# FET_M1.net
KiCad netlist of a schematic drawn in Altium Designer
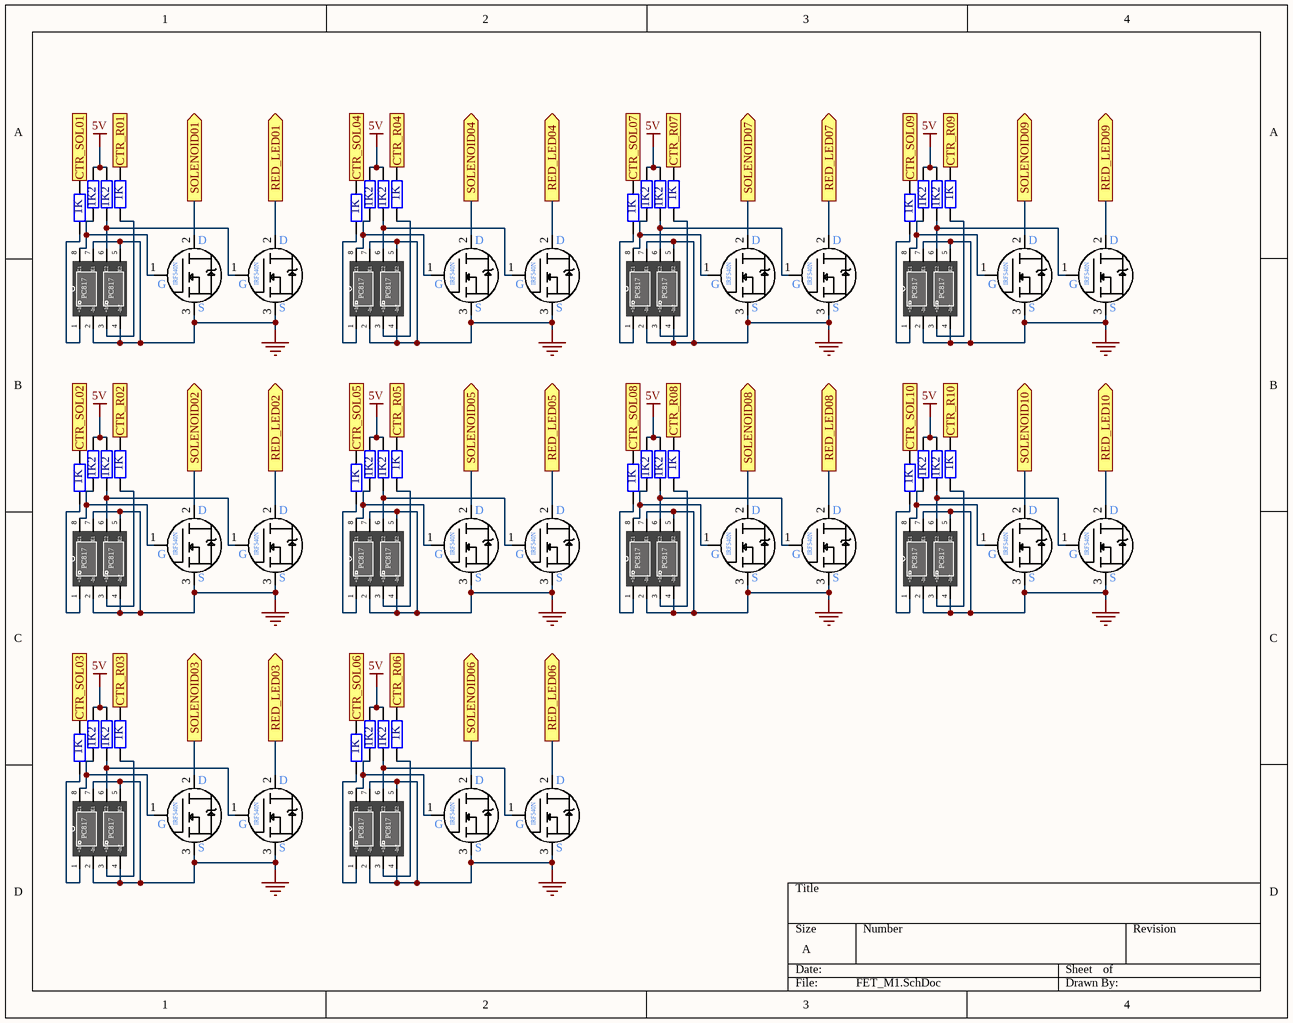
[diagram p0: FET_M1.SchDoc]

(export (version "E")
  (design (tool "Eeschema 10.0.6"))
  (components
    (comp (ref "FET1") (value "5#IRF540N") (footprint "5#IRF540N") (libsource (lib "Sch") (part "5#IRF540N")))
    (comp (ref "FET2") (value "5#IRF540N") (footprint "5#IRF540N") (libsource (lib "Sch") (part "5#IRF540N")))
    (comp (ref "FET3") (value "5#IRF540N") (footprint "5#IRF540N") (libsource (lib "Sch") (part "5#IRF540N")))
    (comp (ref "FET4") (value "5#IRF540N") (footprint "5#IRF540N") (libsource (lib "Sch") (part "5#IRF540N")))
    (comp (ref "FET5") (value "5#IRF540N") (footprint "5#IRF540N") (libsource (lib "Sch") (part "5#IRF540N")))
    (comp (ref "FET6") (value "5#IRF540N") (footprint "5#IRF540N") (libsource (lib "Sch") (part "5#IRF540N")))
    (comp (ref "FET7") (value "5#IRF540N") (footprint "5#IRF540N") (libsource (lib "Sch") (part "5#IRF540N")))
    (comp (ref "FET8") (value "5#IRF540N") (footprint "5#IRF540N") (libsource (lib "Sch") (part "5#IRF540N")))
    (comp (ref "FET9") (value "5#IRF540N") (footprint "5#IRF540N") (libsource (lib "Sch") (part "5#IRF540N")))
    (comp (ref "FET10")
      (value "5#IRF540N")
      (footprint "5#IRF540N")
      (libsource (lib "Sch") (part "5#IRF540N"))
    )
    (comp (ref "FET11")
      (value "5#IRF540N")
      (footprint "5#IRF540N")
      (libsource (lib "Sch") (part "5#IRF540N"))
    )
    (comp (ref "FET12")
      (value "5#IRF540N")
      (footprint "5#IRF540N")
      (libsource (lib "Sch") (part "5#IRF540N"))
    )
    (comp (ref "FET13")
      (value "5#IRF540N")
      (footprint "5#IRF540N")
      (libsource (lib "Sch") (part "5#IRF540N"))
    )
    (comp (ref "FET14")
      (value "5#IRF540N")
      (footprint "5#IRF540N")
      (libsource (lib "Sch") (part "5#IRF540N"))
    )
    (comp (ref "FET15")
      (value "5#IRF540N")
      (footprint "5#IRF540N")
      (libsource (lib "Sch") (part "5#IRF540N"))
    )
    (comp (ref "FET16")
      (value "5#IRF540N")
      (footprint "5#IRF540N")
      (libsource (lib "Sch") (part "5#IRF540N"))
    )
    (comp (ref "FET17")
      (value "5#IRF540N")
      (footprint "5#IRF540N")
      (libsource (lib "Sch") (part "5#IRF540N"))
    )
    (comp (ref "FET18")
      (value "5#IRF540N")
      (footprint "5#IRF540N")
      (libsource (lib "Sch") (part "5#IRF540N"))
    )
    (comp (ref "FET19")
      (value "5#IRF540N")
      (footprint "5#IRF540N")
      (libsource (lib "Sch") (part "5#IRF540N"))
    )
    (comp (ref "FET20")
      (value "5#IRF540N")
      (footprint "5#IRF540N")
      (libsource (lib "Sch") (part "5#IRF540N"))
    )
    (comp (ref "PC1")
      (value "5#Dip8_PC817x2")
      (footprint "5#Dip8_PC817x2")
      (libsource (lib "Sch") (part "5#Dip8_PC817x2"))
    )
    (comp (ref "PC2")
      (value "5#Dip8_PC817x2")
      (footprint "5#Dip8_PC817x2")
      (libsource (lib "Sch") (part "5#Dip8_PC817x2"))
    )
    (comp (ref "PC3")
      (value "5#Dip8_PC817x2")
      (footprint "5#Dip8_PC817x2")
      (libsource (lib "Sch") (part "5#Dip8_PC817x2"))
    )
    (comp (ref "PC4")
      (value "5#Dip8_PC817x2")
      (footprint "5#Dip8_PC817x2")
      (libsource (lib "Sch") (part "5#Dip8_PC817x2"))
    )
    (comp (ref "PC5")
      (value "5#Dip8_PC817x2")
      (footprint "5#Dip8_PC817x2")
      (libsource (lib "Sch") (part "5#Dip8_PC817x2"))
    )
    (comp (ref "PC6")
      (value "5#Dip8_PC817x2")
      (footprint "5#Dip8_PC817x2")
      (libsource (lib "Sch") (part "5#Dip8_PC817x2"))
    )
    (comp (ref "PC7")
      (value "5#Dip8_PC817x2")
      (footprint "5#Dip8_PC817x2")
      (libsource (lib "Sch") (part "5#Dip8_PC817x2"))
    )
    (comp (ref "PC8")
      (value "5#Dip8_PC817x2")
      (footprint "5#Dip8_PC817x2")
      (libsource (lib "Sch") (part "5#Dip8_PC817x2"))
    )
    (comp (ref "PC9")
      (value "5#Dip8_PC817x2")
      (footprint "5#Dip8_PC817x2")
      (libsource (lib "Sch") (part "5#Dip8_PC817x2"))
    )
    (comp (ref "PC10")
      (value "5#Dip8_PC817x2")
      (footprint "5#Dip8_PC817x2")
      (libsource (lib "Sch") (part "5#Dip8_PC817x2"))
    )
    (comp (ref "R18")
      (value "1K")
      (footprint "AXIAL-0.4")
      (description "Resistor")
      (fields (field (name "PUBLISHER") "Altium Limited"))
      (libsource (lib "Miscellaneous Devices") (part "Res2"))
    )
    (comp (ref "R19")
      (value "1K2")
      (footprint "AXIAL-0.4")
      (description "Resistor")
      (fields (field (name "PUBLISHER") "Altium Limited"))
      (libsource (lib "") (part "Res2_1"))
    )
    (comp (ref "R20")
      (value "1K")
      (footprint "AXIAL-0.4")
      (description "Resistor")
      (fields (field (name "PUBLISHER") "Altium Limited"))
      (libsource (lib "Miscellaneous Devices") (part "Res2"))
    )
    (comp (ref "R21")
      (value "1K2")
      (footprint "AXIAL-0.4")
      (description "Resistor")
      (fields (field (name "PUBLISHER") "Altium Limited"))
      (libsource (lib "") (part "Res2_1"))
    )
    (comp (ref "R22")
      (value "1K")
      (footprint "AXIAL-0.4")
      (description "Resistor")
      (fields (field (name "PUBLISHER") "Altium Limited"))
      (libsource (lib "Miscellaneous Devices") (part "Res2"))
    )
    (comp (ref "R23")
      (value "1K2")
      (footprint "AXIAL-0.4")
      (description "Resistor")
      (fields (field (name "PUBLISHER") "Altium Limited"))
      (libsource (lib "") (part "Res2_1"))
    )
    (comp (ref "R24")
      (value "1K")
      (footprint "AXIAL-0.4")
      (description "Resistor")
      (fields (field (name "PUBLISHER") "Altium Limited"))
      (libsource (lib "Miscellaneous Devices") (part "Res2"))
    )
    (comp (ref "R25")
      (value "1K2")
      (footprint "AXIAL-0.4")
      (description "Resistor")
      (fields (field (name "PUBLISHER") "Altium Limited"))
      (libsource (lib "") (part "Res2_1"))
    )
    (comp (ref "R26")
      (value "1K")
      (footprint "AXIAL-0.4")
      (description "Resistor")
      (fields (field (name "PUBLISHER") "Altium Limited"))
      (libsource (lib "Miscellaneous Devices") (part "Res2"))
    )
    (comp (ref "R27")
      (value "1K2")
      (footprint "AXIAL-0.4")
      (description "Resistor")
      (fields (field (name "PUBLISHER") "Altium Limited"))
      (libsource (lib "") (part "Res2_1"))
    )
    (comp (ref "R28")
      (value "1K")
      (footprint "AXIAL-0.4")
      (description "Resistor")
      (fields (field (name "PUBLISHER") "Altium Limited"))
      (libsource (lib "Miscellaneous Devices") (part "Res2"))
    )
    (comp (ref "R29")
      (value "1K2")
      (footprint "AXIAL-0.4")
      (description "Resistor")
      (fields (field (name "PUBLISHER") "Altium Limited"))
      (libsource (lib "") (part "Res2_1"))
    )
    (comp (ref "R30")
      (value "1K")
      (footprint "AXIAL-0.4")
      (description "Resistor")
      (fields (field (name "PUBLISHER") "Altium Limited"))
      (libsource (lib "Miscellaneous Devices") (part "Res2"))
    )
    (comp (ref "R31")
      (value "1K2")
      (footprint "AXIAL-0.4")
      (description "Resistor")
      (fields (field (name "PUBLISHER") "Altium Limited"))
      (libsource (lib "") (part "Res2_1"))
    )
    (comp (ref "R32")
      (value "1K")
      (footprint "AXIAL-0.4")
      (description "Resistor")
      (fields (field (name "PUBLISHER") "Altium Limited"))
      (libsource (lib "Miscellaneous Devices") (part "Res2"))
    )
    (comp (ref "R33")
      (value "1K2")
      (footprint "AXIAL-0.4")
      (description "Resistor")
      (fields (field (name "PUBLISHER") "Altium Limited"))
      (libsource (lib "") (part "Res2_1"))
    )
    (comp (ref "R34")
      (value "1K")
      (footprint "AXIAL-0.4")
      (description "Resistor")
      (fields (field (name "PUBLISHER") "Altium Limited"))
      (libsource (lib "Miscellaneous Devices") (part "Res2"))
    )
    (comp (ref "R35")
      (value "1K2")
      (footprint "AXIAL-0.4")
      (description "Resistor")
      (fields (field (name "PUBLISHER") "Altium Limited"))
      (libsource (lib "") (part "Res2_1"))
    )
    (comp (ref "R36")
      (value "1K")
      (footprint "AXIAL-0.4")
      (description "Resistor")
      (fields (field (name "PUBLISHER") "Altium Limited"))
      (libsource (lib "Miscellaneous Devices") (part "Res2"))
    )
    (comp (ref "R37")
      (value "1K2")
      (footprint "AXIAL-0.4")
      (description "Resistor")
      (fields (field (name "PUBLISHER") "Altium Limited"))
      (libsource (lib "") (part "Res2_1"))
    )
    (comp (ref "R38")
      (value "1K")
      (footprint "AXIAL-0.4")
      (description "Resistor")
      (fields (field (name "PUBLISHER") "Altium Limited"))
      (libsource (lib "Miscellaneous Devices") (part "Res2"))
    )
    (comp (ref "R39")
      (value "1K2")
      (footprint "AXIAL-0.4")
      (description "Resistor")
      (fields (field (name "PUBLISHER") "Altium Limited"))
      (libsource (lib "") (part "Res2_1"))
    )
    (comp (ref "R40")
      (value "1K")
      (footprint "AXIAL-0.4")
      (description "Resistor")
      (fields (field (name "PUBLISHER") "Altium Limited"))
      (libsource (lib "Miscellaneous Devices") (part "Res2"))
    )
    (comp (ref "R41")
      (value "1K2")
      (footprint "AXIAL-0.4")
      (description "Resistor")
      (fields (field (name "PUBLISHER") "Altium Limited"))
      (libsource (lib "") (part "Res2_1"))
    )
    (comp (ref "R42")
      (value "1K")
      (footprint "AXIAL-0.4")
      (description "Resistor")
      (fields (field (name "PUBLISHER") "Altium Limited"))
      (libsource (lib "Miscellaneous Devices") (part "Res2"))
    )
    (comp (ref "R43")
      (value "1K2")
      (footprint "AXIAL-0.4")
      (description "Resistor")
      (fields (field (name "PUBLISHER") "Altium Limited"))
      (libsource (lib "") (part "Res2_1"))
    )
    (comp (ref "R44")
      (value "1K")
      (footprint "AXIAL-0.4")
      (description "Resistor")
      (fields (field (name "PUBLISHER") "Altium Limited"))
      (libsource (lib "Miscellaneous Devices") (part "Res2"))
    )
    (comp (ref "R45")
      (value "1K2")
      (footprint "AXIAL-0.4")
      (description "Resistor")
      (fields (field (name "PUBLISHER") "Altium Limited"))
      (libsource (lib "") (part "Res2_1"))
    )
    (comp (ref "R46")
      (value "1K")
      (footprint "AXIAL-0.4")
      (description "Resistor")
      (fields (field (name "PUBLISHER") "Altium Limited"))
      (libsource (lib "Miscellaneous Devices") (part "Res2"))
    )
    (comp (ref "R47")
      (value "1K2")
      (footprint "AXIAL-0.4")
      (description "Resistor")
      (fields (field (name "PUBLISHER") "Altium Limited"))
      (libsource (lib "") (part "Res2_1"))
    )
    (comp (ref "R48")
      (value "1K")
      (footprint "AXIAL-0.4")
      (description "Resistor")
      (fields (field (name "PUBLISHER") "Altium Limited"))
      (libsource (lib "Miscellaneous Devices") (part "Res2"))
    )
    (comp (ref "R49")
      (value "1K2")
      (footprint "AXIAL-0.4")
      (description "Resistor")
      (fields (field (name "PUBLISHER") "Altium Limited"))
      (libsource (lib "") (part "Res2_1"))
    )
    (comp (ref "R50")
      (value "1K")
      (footprint "AXIAL-0.4")
      (description "Resistor")
      (fields (field (name "PUBLISHER") "Altium Limited"))
      (libsource (lib "Miscellaneous Devices") (part "Res2"))
    )
    (comp (ref "R51")
      (value "1K2")
      (footprint "AXIAL-0.4")
      (description "Resistor")
      (fields (field (name "PUBLISHER") "Altium Limited"))
      (libsource (lib "") (part "Res2_1"))
    )
    (comp (ref "R52")
      (value "1K")
      (footprint "AXIAL-0.4")
      (description "Resistor")
      (fields (field (name "PUBLISHER") "Altium Limited"))
      (libsource (lib "Miscellaneous Devices") (part "Res2"))
    )
    (comp (ref "R53")
      (value "1K2")
      (footprint "AXIAL-0.4")
      (description "Resistor")
      (fields (field (name "PUBLISHER") "Altium Limited"))
      (libsource (lib "") (part "Res2_1"))
    )
    (comp (ref "R54")
      (value "1K")
      (footprint "AXIAL-0.4")
      (description "Resistor")
      (fields (field (name "PUBLISHER") "Altium Limited"))
      (libsource (lib "Miscellaneous Devices") (part "Res2"))
    )
    (comp (ref "R55")
      (value "1K2")
      (footprint "AXIAL-0.4")
      (description "Resistor")
      (fields (field (name "PUBLISHER") "Altium Limited"))
      (libsource (lib "") (part "Res2_1"))
    )
    (comp (ref "R56")
      (value "1K")
      (footprint "AXIAL-0.4")
      (description "Resistor")
      (fields (field (name "PUBLISHER") "Altium Limited"))
      (libsource (lib "Miscellaneous Devices") (part "Res2"))
    )
    (comp (ref "R57")
      (value "1K2")
      (footprint "AXIAL-0.4")
      (description "Resistor")
      (fields (field (name "PUBLISHER") "Altium Limited"))
      (libsource (lib "") (part "Res2_1"))
    )
  )
  (nets
    (net (code "1") (name "/CTR_R01") (class "Default")
      (node (ref "R26") (pin "1") (pinfunction "1_1") (pintype "passive"))
    )
    (net (code "2") (name "/CTR_R02") (class "Default")
      (node (ref "R28") (pin "1") (pinfunction "1_1") (pintype "passive"))
    )
    (net (code "3") (name "/CTR_R03") (class "Default")
      (node (ref "R30") (pin "1") (pinfunction "1_1") (pintype "passive"))
    )
    (net (code "4") (name "/CTR_R04") (class "Default")
      (node (ref "R32") (pin "1") (pinfunction "1_1") (pintype "passive"))
    )
    (net (code "5") (name "/CTR_R05") (class "Default")
      (node (ref "R42") (pin "1") (pinfunction "1_1") (pintype "passive"))
    )
    (net (code "6") (name "/CTR_R06") (class "Default")
      (node (ref "R44") (pin "1") (pinfunction "1_1") (pintype "passive"))
    )
    (net (code "7") (name "/CTR_R07") (class "Default")
      (node (ref "R46") (pin "1") (pinfunction "1_1") (pintype "passive"))
    )
    (net (code "8") (name "/CTR_R08") (class "Default")
      (node (ref "R48") (pin "1") (pinfunction "1_1") (pintype "passive"))
    )
    (net (code "9") (name "/CTR_R09") (class "Default")
      (node (ref "R54") (pin "1") (pinfunction "1_1") (pintype "passive"))
    )
    (net (code "10") (name "/CTR_R10") (class "Default")
      (node (ref "R56") (pin "1") (pinfunction "1_1") (pintype "passive"))
    )
    (net (code "11") (name "/CTR_SOL01") (class "Default")
      (node (ref "R18") (pin "1") (pinfunction "1_1") (pintype "passive"))
    )
    (net (code "12") (name "/CTR_SOL02") (class "Default")
      (node (ref "R20") (pin "1") (pinfunction "1_1") (pintype "passive"))
    )
    (net (code "13") (name "/CTR_SOL03") (class "Default")
      (node (ref "R22") (pin "1") (pinfunction "1_1") (pintype "passive"))
    )
    (net (code "14") (name "/CTR_SOL04") (class "Default")
      (node (ref "R24") (pin "1") (pinfunction "1_1") (pintype "passive"))
    )
    (net (code "15") (name "/CTR_SOL05") (class "Default")
      (node (ref "R34") (pin "1") (pinfunction "1_1") (pintype "passive"))
    )
    (net (code "16") (name "/CTR_SOL06") (class "Default")
      (node (ref "R36") (pin "1") (pinfunction "1_1") (pintype "passive"))
    )
    (net (code "17") (name "/CTR_SOL07") (class "Default")
      (node (ref "R38") (pin "1") (pinfunction "1_1") (pintype "passive"))
    )
    (net (code "18") (name "/CTR_SOL08") (class "Default")
      (node (ref "R40") (pin "1") (pinfunction "1_1") (pintype "passive"))
    )
    (net (code "19") (name "/CTR_SOL09") (class "Default")
      (node (ref "R50") (pin "1") (pinfunction "1_1") (pintype "passive"))
    )
    (net (code "20") (name "/CTR_SOL10") (class "Default")
      (node (ref "R52") (pin "1") (pinfunction "1_1") (pintype "passive"))
    )
    (net (code "21") (name "/RED_LED01") (class "Default")
      (node (ref "FET2") (pin "2") (pinfunction "D_2") (pintype "passive"))
    )
    (net (code "22") (name "/RED_LED02") (class "Default")
      (node (ref "FET4") (pin "2") (pinfunction "D_2") (pintype "passive"))
    )
    (net (code "23") (name "/RED_LED03") (class "Default")
      (node (ref "FET6") (pin "2") (pinfunction "D_2") (pintype "passive"))
    )
    (net (code "24") (name "/RED_LED04") (class "Default")
      (node (ref "FET8") (pin "2") (pinfunction "D_2") (pintype "passive"))
    )
    (net (code "25") (name "/RED_LED05") (class "Default")
      (node (ref "FET10") (pin "2") (pinfunction "D_2") (pintype "passive"))
    )
    (net (code "26") (name "/RED_LED06") (class "Default")
      (node (ref "FET12") (pin "2") (pinfunction "D_2") (pintype "passive"))
    )
    (net (code "27") (name "/RED_LED07") (class "Default")
      (node (ref "FET14") (pin "2") (pinfunction "D_2") (pintype "passive"))
    )
    (net (code "28") (name "/RED_LED08") (class "Default")
      (node (ref "FET16") (pin "2") (pinfunction "D_2") (pintype "passive"))
    )
    (net (code "29") (name "/RED_LED09") (class "Default")
      (node (ref "FET18") (pin "2") (pinfunction "D_2") (pintype "passive"))
    )
    (net (code "30") (name "/RED_LED10") (class "Default")
      (node (ref "FET20") (pin "2") (pinfunction "D_2") (pintype "passive"))
    )
    (net (code "31") (name "/SOLENOID01") (class "Default")
      (node (ref "FET1") (pin "2") (pinfunction "D_2") (pintype "passive"))
    )
    (net (code "32") (name "/SOLENOID02") (class "Default")
      (node (ref "FET3") (pin "2") (pinfunction "D_2") (pintype "passive"))
    )
    (net (code "33") (name "/SOLENOID03") (class "Default")
      (node (ref "FET5") (pin "2") (pinfunction "D_2") (pintype "passive"))
    )
    (net (code "34") (name "/SOLENOID04") (class "Default")
      (node (ref "FET7") (pin "2") (pinfunction "D_2") (pintype "passive"))
    )
    (net (code "35") (name "/SOLENOID05") (class "Default")
      (node (ref "FET9") (pin "2") (pinfunction "D_2") (pintype "passive"))
    )
    (net (code "36") (name "/SOLENOID06") (class "Default")
      (node (ref "FET11") (pin "2") (pinfunction "D_2") (pintype "passive"))
    )
    (net (code "37") (name "/SOLENOID07") (class "Default")
      (node (ref "FET13") (pin "2") (pinfunction "D_2") (pintype "passive"))
    )
    (net (code "38") (name "/SOLENOID08") (class "Default")
      (node (ref "FET15") (pin "2") (pinfunction "D_2") (pintype "passive"))
    )
    (net (code "39") (name "/SOLENOID09") (class "Default")
      (node (ref "FET17") (pin "2") (pinfunction "D_2") (pintype "passive"))
    )
    (net (code "40") (name "/SOLENOID10") (class "Default")
      (node (ref "FET19") (pin "2") (pinfunction "D_2") (pintype "passive"))
    )
    (net (code "41") (name "5V") (class "Default")
      (node (ref "R19") (pin "2") (pinfunction "2_2") (pintype "passive"))
      (node (ref "R21") (pin "2") (pinfunction "2_2") (pintype "passive"))
      (node (ref "R23") (pin "2") (pinfunction "2_2") (pintype "passive"))
      (node (ref "R25") (pin "2") (pinfunction "2_2") (pintype "passive"))
      (node (ref "R27") (pin "2") (pinfunction "2_2") (pintype "passive"))
      (node (ref "R29") (pin "2") (pinfunction "2_2") (pintype "passive"))
      (node (ref "R31") (pin "2") (pinfunction "2_2") (pintype "passive"))
      (node (ref "R33") (pin "2") (pinfunction "2_2") (pintype "passive"))
      (node (ref "R35") (pin "2") (pinfunction "2_2") (pintype "passive"))
      (node (ref "R37") (pin "2") (pinfunction "2_2") (pintype "passive"))
      (node (ref "R39") (pin "2") (pinfunction "2_2") (pintype "passive"))
      (node (ref "R41") (pin "2") (pinfunction "2_2") (pintype "passive"))
      (node (ref "R43") (pin "2") (pinfunction "2_2") (pintype "passive"))
      (node (ref "R45") (pin "2") (pinfunction "2_2") (pintype "passive"))
      (node (ref "R47") (pin "2") (pinfunction "2_2") (pintype "passive"))
      (node (ref "R49") (pin "2") (pinfunction "2_2") (pintype "passive"))
      (node (ref "R51") (pin "2") (pinfunction "2_2") (pintype "passive"))
      (node (ref "R53") (pin "2") (pinfunction "2_2") (pintype "passive"))
      (node (ref "R55") (pin "2") (pinfunction "2_2") (pintype "passive"))
      (node (ref "R57") (pin "2") (pinfunction "2_2") (pintype "passive"))
    )
    (net (code "42") (name "GND") (class "Default")
      (node (ref "FET1") (pin "3") (pinfunction "S_3") (pintype "passive"))
      (node (ref "FET10") (pin "3") (pinfunction "S_3") (pintype "passive"))
      (node (ref "FET11") (pin "3") (pinfunction "S_3") (pintype "passive"))
      (node (ref "FET12") (pin "3") (pinfunction "S_3") (pintype "passive"))
      (node (ref "FET13") (pin "3") (pinfunction "S_3") (pintype "passive"))
      (node (ref "FET14") (pin "3") (pinfunction "S_3") (pintype "passive"))
      (node (ref "FET15") (pin "3") (pinfunction "S_3") (pintype "passive"))
      (node (ref "FET16") (pin "3") (pinfunction "S_3") (pintype "passive"))
      (node (ref "FET17") (pin "3") (pinfunction "S_3") (pintype "passive"))
      (node (ref "FET18") (pin "3") (pinfunction "S_3") (pintype "passive"))
      (node (ref "FET19") (pin "3") (pinfunction "S_3") (pintype "passive"))
      (node (ref "FET2") (pin "3") (pinfunction "S_3") (pintype "passive"))
      (node (ref "FET20") (pin "3") (pinfunction "S_3") (pintype "passive"))
      (node (ref "FET3") (pin "3") (pinfunction "S_3") (pintype "passive"))
      (node (ref "FET4") (pin "3") (pinfunction "S_3") (pintype "passive"))
      (node (ref "FET5") (pin "3") (pinfunction "S_3") (pintype "passive"))
      (node (ref "FET6") (pin "3") (pinfunction "S_3") (pintype "passive"))
      (node (ref "FET7") (pin "3") (pinfunction "S_3") (pintype "passive"))
      (node (ref "FET8") (pin "3") (pinfunction "S_3") (pintype "passive"))
      (node (ref "FET9") (pin "3") (pinfunction "S_3") (pintype "passive"))
      (node (ref "PC1") (pin "2") (pinfunction "-In1_2") (pintype "passive"))
      (node (ref "PC1") (pin "4") (pinfunction "-In2_4") (pintype "passive"))
      (node (ref "PC1") (pin "5") (pinfunction "E2_5") (pintype "passive"))
      (node (ref "PC1") (pin "7") (pinfunction "E1_7") (pintype "passive"))
      (node (ref "PC10") (pin "2") (pinfunction "-In1_2") (pintype "passive"))
      (node (ref "PC10") (pin "4") (pinfunction "-In2_4") (pintype "passive"))
      (node (ref "PC10") (pin "5") (pinfunction "E2_5") (pintype "passive"))
      (node (ref "PC10") (pin "7") (pinfunction "E1_7") (pintype "passive"))
      (node (ref "PC2") (pin "2") (pinfunction "-In1_2") (pintype "passive"))
      (node (ref "PC2") (pin "4") (pinfunction "-In2_4") (pintype "passive"))
      (node (ref "PC2") (pin "5") (pinfunction "E2_5") (pintype "passive"))
      (node (ref "PC2") (pin "7") (pinfunction "E1_7") (pintype "passive"))
      (node (ref "PC3") (pin "2") (pinfunction "-In1_2") (pintype "passive"))
      (node (ref "PC3") (pin "4") (pinfunction "-In2_4") (pintype "passive"))
      (node (ref "PC3") (pin "5") (pinfunction "E2_5") (pintype "passive"))
      (node (ref "PC3") (pin "7") (pinfunction "E1_7") (pintype "passive"))
      (node (ref "PC4") (pin "2") (pinfunction "-In1_2") (pintype "passive"))
      (node (ref "PC4") (pin "4") (pinfunction "-In2_4") (pintype "passive"))
      (node (ref "PC4") (pin "5") (pinfunction "E2_5") (pintype "passive"))
      (node (ref "PC4") (pin "7") (pinfunction "E1_7") (pintype "passive"))
      (node (ref "PC5") (pin "2") (pinfunction "-In1_2") (pintype "passive"))
      (node (ref "PC5") (pin "4") (pinfunction "-In2_4") (pintype "passive"))
      (node (ref "PC5") (pin "5") (pinfunction "E2_5") (pintype "passive"))
      (node (ref "PC5") (pin "7") (pinfunction "E1_7") (pintype "passive"))
      (node (ref "PC6") (pin "2") (pinfunction "-In1_2") (pintype "passive"))
      (node (ref "PC6") (pin "4") (pinfunction "-In2_4") (pintype "passive"))
      (node (ref "PC6") (pin "5") (pinfunction "E2_5") (pintype "passive"))
      (node (ref "PC6") (pin "7") (pinfunction "E1_7") (pintype "passive"))
      (node (ref "PC7") (pin "2") (pinfunction "-In1_2") (pintype "passive"))
      (node (ref "PC7") (pin "4") (pinfunction "-In2_4") (pintype "passive"))
      (node (ref "PC7") (pin "5") (pinfunction "E2_5") (pintype "passive"))
      (node (ref "PC7") (pin "7") (pinfunction "E1_7") (pintype "passive"))
      (node (ref "PC8") (pin "2") (pinfunction "-In1_2") (pintype "passive"))
      (node (ref "PC8") (pin "4") (pinfunction "-In2_4") (pintype "passive"))
      (node (ref "PC8") (pin "5") (pinfunction "E2_5") (pintype "passive"))
      (node (ref "PC8") (pin "7") (pinfunction "E1_7") (pintype "passive"))
      (node (ref "PC9") (pin "2") (pinfunction "-In1_2") (pintype "passive"))
      (node (ref "PC9") (pin "4") (pinfunction "-In2_4") (pintype "passive"))
      (node (ref "PC9") (pin "5") (pinfunction "E2_5") (pintype "passive"))
      (node (ref "PC9") (pin "7") (pinfunction "E1_7") (pintype "passive"))
    )
    (net (code "43") (name "Net-(FET1-G)") (class "Default")
      (node (ref "FET1") (pin "1") (pinfunction "G_1") (pintype "passive"))
      (node (ref "PC1") (pin "8") (pinfunction "C1_8") (pintype "passive"))
      (node (ref "R19") (pin "1") (pinfunction "1_1") (pintype "passive"))
    )
    (net (code "44") (name "Net-(FET2-G)") (class "Default")
      (node (ref "FET2") (pin "1") (pinfunction "G_1") (pintype "passive"))
      (node (ref "PC1") (pin "6") (pinfunction "C2_6") (pintype "passive"))
      (node (ref "R27") (pin "1") (pinfunction "1_1") (pintype "passive"))
    )
    (net (code "45") (name "Net-(FET3-G)") (class "Default")
      (node (ref "FET3") (pin "1") (pinfunction "G_1") (pintype "passive"))
      (node (ref "PC2") (pin "8") (pinfunction "C1_8") (pintype "passive"))
      (node (ref "R21") (pin "1") (pinfunction "1_1") (pintype "passive"))
    )
    (net (code "46") (name "Net-(FET4-G)") (class "Default")
      (node (ref "FET4") (pin "1") (pinfunction "G_1") (pintype "passive"))
      (node (ref "PC2") (pin "6") (pinfunction "C2_6") (pintype "passive"))
      (node (ref "R29") (pin "1") (pinfunction "1_1") (pintype "passive"))
    )
    (net (code "47") (name "Net-(FET5-G)") (class "Default")
      (node (ref "FET5") (pin "1") (pinfunction "G_1") (pintype "passive"))
      (node (ref "PC3") (pin "8") (pinfunction "C1_8") (pintype "passive"))
      (node (ref "R23") (pin "1") (pinfunction "1_1") (pintype "passive"))
    )
    (net (code "48") (name "Net-(FET6-G)") (class "Default")
      (node (ref "FET6") (pin "1") (pinfunction "G_1") (pintype "passive"))
      (node (ref "PC3") (pin "6") (pinfunction "C2_6") (pintype "passive"))
      (node (ref "R31") (pin "1") (pinfunction "1_1") (pintype "passive"))
    )
    (net (code "49") (name "Net-(FET7-G)") (class "Default")
      (node (ref "FET7") (pin "1") (pinfunction "G_1") (pintype "passive"))
      (node (ref "PC4") (pin "8") (pinfunction "C1_8") (pintype "passive"))
      (node (ref "R25") (pin "1") (pinfunction "1_1") (pintype "passive"))
    )
    (net (code "50") (name "Net-(FET8-G)") (class "Default")
      (node (ref "FET8") (pin "1") (pinfunction "G_1") (pintype "passive"))
      (node (ref "PC4") (pin "6") (pinfunction "C2_6") (pintype "passive"))
      (node (ref "R33") (pin "1") (pinfunction "1_1") (pintype "passive"))
    )
    (net (code "51") (name "Net-(FET9-G)") (class "Default")
      (node (ref "FET9") (pin "1") (pinfunction "G_1") (pintype "passive"))
      (node (ref "PC5") (pin "8") (pinfunction "C1_8") (pintype "passive"))
      (node (ref "R35") (pin "1") (pinfunction "1_1") (pintype "passive"))
    )
    (net (code "52") (name "Net-(FET10-G)") (class "Default")
      (node (ref "FET10") (pin "1") (pinfunction "G_1") (pintype "passive"))
      (node (ref "PC5") (pin "6") (pinfunction "C2_6") (pintype "passive"))
      (node (ref "R43") (pin "1") (pinfunction "1_1") (pintype "passive"))
    )
    (net (code "53") (name "Net-(FET11-G)") (class "Default")
      (node (ref "FET11") (pin "1") (pinfunction "G_1") (pintype "passive"))
      (node (ref "PC6") (pin "8") (pinfunction "C1_8") (pintype "passive"))
      (node (ref "R37") (pin "1") (pinfunction "1_1") (pintype "passive"))
    )
    (net (code "54") (name "Net-(FET12-G)") (class "Default")
      (node (ref "FET12") (pin "1") (pinfunction "G_1") (pintype "passive"))
      (node (ref "PC6") (pin "6") (pinfunction "C2_6") (pintype "passive"))
      (node (ref "R45") (pin "1") (pinfunction "1_1") (pintype "passive"))
    )
    (net (code "55") (name "Net-(FET13-G)") (class "Default")
      (node (ref "FET13") (pin "1") (pinfunction "G_1") (pintype "passive"))
      (node (ref "PC7") (pin "8") (pinfunction "C1_8") (pintype "passive"))
      (node (ref "R39") (pin "1") (pinfunction "1_1") (pintype "passive"))
    )
    (net (code "56") (name "Net-(FET14-G)") (class "Default")
      (node (ref "FET14") (pin "1") (pinfunction "G_1") (pintype "passive"))
      (node (ref "PC7") (pin "6") (pinfunction "C2_6") (pintype "passive"))
      (node (ref "R47") (pin "1") (pinfunction "1_1") (pintype "passive"))
    )
    (net (code "57") (name "Net-(FET15-G)") (class "Default")
      (node (ref "FET15") (pin "1") (pinfunction "G_1") (pintype "passive"))
      (node (ref "PC8") (pin "8") (pinfunction "C1_8") (pintype "passive"))
      (node (ref "R41") (pin "1") (pinfunction "1_1") (pintype "passive"))
    )
    (net (code "58") (name "Net-(FET16-G)") (class "Default")
      (node (ref "FET16") (pin "1") (pinfunction "G_1") (pintype "passive"))
      (node (ref "PC8") (pin "6") (pinfunction "C2_6") (pintype "passive"))
      (node (ref "R49") (pin "1") (pinfunction "1_1") (pintype "passive"))
    )
    (net (code "59") (name "Net-(FET17-G)") (class "Default")
      (node (ref "FET17") (pin "1") (pinfunction "G_1") (pintype "passive"))
      (node (ref "PC9") (pin "8") (pinfunction "C1_8") (pintype "passive"))
      (node (ref "R51") (pin "1") (pinfunction "1_1") (pintype "passive"))
    )
    (net (code "60") (name "Net-(FET18-G)") (class "Default")
      (node (ref "FET18") (pin "1") (pinfunction "G_1") (pintype "passive"))
      (node (ref "PC9") (pin "6") (pinfunction "C2_6") (pintype "passive"))
      (node (ref "R55") (pin "1") (pinfunction "1_1") (pintype "passive"))
    )
    (net (code "61") (name "Net-(FET19-G)") (class "Default")
      (node (ref "FET19") (pin "1") (pinfunction "G_1") (pintype "passive"))
      (node (ref "PC10") (pin "8") (pinfunction "C1_8") (pintype "passive"))
      (node (ref "R53") (pin "1") (pinfunction "1_1") (pintype "passive"))
    )
    (net (code "62") (name "Net-(FET20-G)") (class "Default")
      (node (ref "FET20") (pin "1") (pinfunction "G_1") (pintype "passive"))
      (node (ref "PC10") (pin "6") (pinfunction "C2_6") (pintype "passive"))
      (node (ref "R57") (pin "1") (pinfunction "1_1") (pintype "passive"))
    )
    (net (code "63") (name "Net-(PC1-+In1)") (class "Default")
      (node (ref "PC1") (pin "1") (pinfunction "+In1_1") (pintype "passive"))
      (node (ref "R18") (pin "2") (pinfunction "2_2") (pintype "passive"))
    )
    (net (code "64") (name "Net-(PC1-+In2)") (class "Default")
      (node (ref "PC1") (pin "3") (pinfunction "+In2_3") (pintype "passive"))
      (node (ref "R26") (pin "2") (pinfunction "2_2") (pintype "passive"))
    )
    (net (code "65") (name "Net-(PC2-+In1)") (class "Default")
      (node (ref "PC2") (pin "1") (pinfunction "+In1_1") (pintype "passive"))
      (node (ref "R20") (pin "2") (pinfunction "2_2") (pintype "passive"))
    )
    (net (code "66") (name "Net-(PC2-+In2)") (class "Default")
      (node (ref "PC2") (pin "3") (pinfunction "+In2_3") (pintype "passive"))
      (node (ref "R28") (pin "2") (pinfunction "2_2") (pintype "passive"))
    )
    (net (code "67") (name "Net-(PC3-+In1)") (class "Default")
      (node (ref "PC3") (pin "1") (pinfunction "+In1_1") (pintype "passive"))
      (node (ref "R22") (pin "2") (pinfunction "2_2") (pintype "passive"))
    )
    (net (code "68") (name "Net-(PC3-+In2)") (class "Default")
      (node (ref "PC3") (pin "3") (pinfunction "+In2_3") (pintype "passive"))
      (node (ref "R30") (pin "2") (pinfunction "2_2") (pintype "passive"))
    )
    (net (code "69") (name "Net-(PC4-+In1)") (class "Default")
      (node (ref "PC4") (pin "1") (pinfunction "+In1_1") (pintype "passive"))
      (node (ref "R24") (pin "2") (pinfunction "2_2") (pintype "passive"))
    )
    (net (code "70") (name "Net-(PC4-+In2)") (class "Default")
      (node (ref "PC4") (pin "3") (pinfunction "+In2_3") (pintype "passive"))
      (node (ref "R32") (pin "2") (pinfunction "2_2") (pintype "passive"))
    )
    (net (code "71") (name "Net-(PC5-+In1)") (class "Default")
      (node (ref "PC5") (pin "1") (pinfunction "+In1_1") (pintype "passive"))
      (node (ref "R34") (pin "2") (pinfunction "2_2") (pintype "passive"))
    )
    (net (code "72") (name "Net-(PC5-+In2)") (class "Default")
      (node (ref "PC5") (pin "3") (pinfunction "+In2_3") (pintype "passive"))
      (node (ref "R42") (pin "2") (pinfunction "2_2") (pintype "passive"))
    )
    (net (code "73") (name "Net-(PC6-+In1)") (class "Default")
      (node (ref "PC6") (pin "1") (pinfunction "+In1_1") (pintype "passive"))
      (node (ref "R36") (pin "2") (pinfunction "2_2") (pintype "passive"))
    )
    (net (code "74") (name "Net-(PC6-+In2)") (class "Default")
      (node (ref "PC6") (pin "3") (pinfunction "+In2_3") (pintype "passive"))
      (node (ref "R44") (pin "2") (pinfunction "2_2") (pintype "passive"))
    )
    (net (code "75") (name "Net-(PC7-+In1)") (class "Default")
      (node (ref "PC7") (pin "1") (pinfunction "+In1_1") (pintype "passive"))
      (node (ref "R38") (pin "2") (pinfunction "2_2") (pintype "passive"))
    )
    (net (code "76") (name "Net-(PC7-+In2)") (class "Default")
      (node (ref "PC7") (pin "3") (pinfunction "+In2_3") (pintype "passive"))
      (node (ref "R46") (pin "2") (pinfunction "2_2") (pintype "passive"))
    )
    (net (code "77") (name "Net-(PC8-+In1)") (class "Default")
      (node (ref "PC8") (pin "1") (pinfunction "+In1_1") (pintype "passive"))
      (node (ref "R40") (pin "2") (pinfunction "2_2") (pintype "passive"))
    )
    (net (code "78") (name "Net-(PC8-+In2)") (class "Default")
      (node (ref "PC8") (pin "3") (pinfunction "+In2_3") (pintype "passive"))
      (node (ref "R48") (pin "2") (pinfunction "2_2") (pintype "passive"))
    )
    (net (code "79") (name "Net-(PC9-+In1)") (class "Default")
      (node (ref "PC9") (pin "1") (pinfunction "+In1_1") (pintype "passive"))
      (node (ref "R50") (pin "2") (pinfunction "2_2") (pintype "passive"))
    )
    (net (code "80") (name "Net-(PC9-+In2)") (class "Default")
      (node (ref "PC9") (pin "3") (pinfunction "+In2_3") (pintype "passive"))
      (node (ref "R54") (pin "2") (pinfunction "2_2") (pintype "passive"))
    )
    (net (code "81") (name "Net-(PC10-+In1)") (class "Default")
      (node (ref "PC10") (pin "1") (pinfunction "+In1_1") (pintype "passive"))
      (node (ref "R52") (pin "2") (pinfunction "2_2") (pintype "passive"))
    )
    (net (code "82") (name "Net-(PC10-+In2)") (class "Default")
      (node (ref "PC10") (pin "3") (pinfunction "+In2_3") (pintype "passive"))
      (node (ref "R56") (pin "2") (pinfunction "2_2") (pintype "passive"))
    )
  )
)
